# Sheet4_Audio_In.net
KiCad netlist of a schematic drawn in Altium Designer
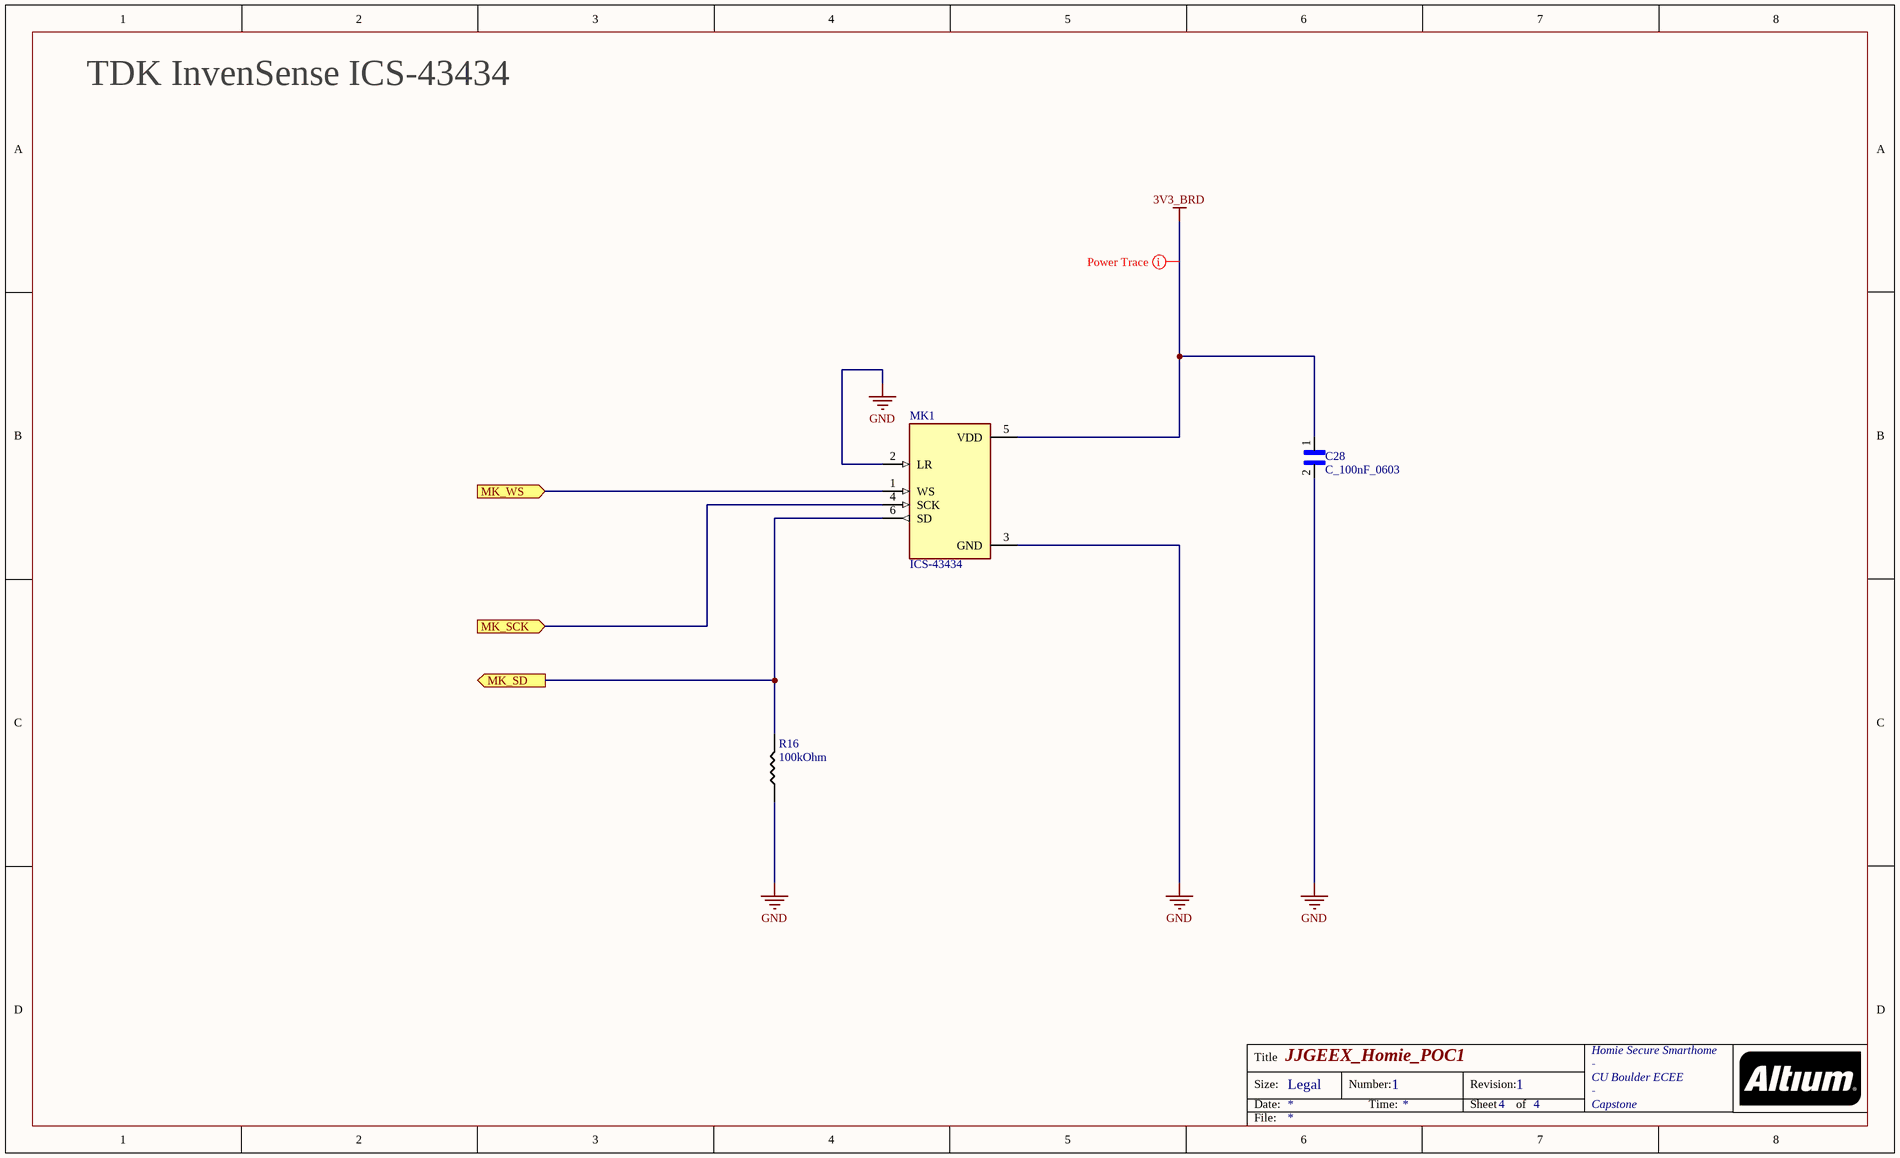
[diagram p0: Sheet4_Audio_In.SchDoc]

(export (version "E")
  (design (tool "Eeschema 10.0.6"))
  (components
    (comp (ref "C28")
      (value "C_100nF_0603")
      (footprint "CAPC1608X90")
      (description "0.1礔/100nF  卤10% 50V Ceramic Capacitor X7R 0603 _1608 Metric_")
      (fields (field (name "DIGI-KEY_PART_NUMBER") "311-1344-1-ND") (field (name "MP") "CC0603KRX7R9BB104"))
      (libsource (lib "Homie_IntegratedLibraryV2") (part "C_100nF_0603"))
    )
    (comp (ref "MK1")
      (value "ICS-43434")
      (footprint "MIC_ICS-43434")
      (fields (field (name "MF") "TDK InvenSense"))
      (libsource (lib "Homie_IntegratedLibraryV2") (part "ICS-43434"))
    )
    (comp (ref "R16")
      (value "100kOhm")
      (footprint "R0603")
      (description "100kOhm +-1%")
      (fields (field (name "MFR") "Uniroyal") (field (name "Comment") "100 kOhm"))
      (libsource (lib "Homie_IntegratedLibraryV2") (part "R_100kOhm_0603"))
    )
  )
  (nets
    (net (code "1") (name "/MK_SCK") (class "Default")
      (node (ref "MK1") (pin "4") (pinfunction "SCK_4") (pintype "input"))
    )
    (net (code "2") (name "/MK_SD") (class "Default")
      (node (ref "MK1") (pin "6") (pinfunction "SD_6") (pintype "output"))
      (node (ref "R16") (pin "2") (pinfunction "2_2") (pintype "passive"))
    )
    (net (code "3") (name "/MK_WS") (class "Default")
      (node (ref "MK1") (pin "1") (pinfunction "WS_1") (pintype "input"))
    )
    (net (code "4") (name "3V3_BRD") (class "Default")
      (node (ref "C28") (pin "1") (pinfunction "1_1") (pintype "passive"))
      (node (ref "MK1") (pin "5") (pinfunction "VDD_5") (pintype "power_in"))
    )
    (net (code "5") (name "GND") (class "Default")
      (node (ref "C28") (pin "2") (pinfunction "2_2") (pintype "passive"))
      (node (ref "MK1") (pin "2") (pinfunction "LR_2") (pintype "input"))
      (node (ref "MK1") (pin "3") (pinfunction "GND_3") (pintype "power_in"))
      (node (ref "R16") (pin "1") (pinfunction "1_1") (pintype "passive"))
    )
  )
)
